# Main.net
KiCad netlist of a schematic drawn in EAGLE
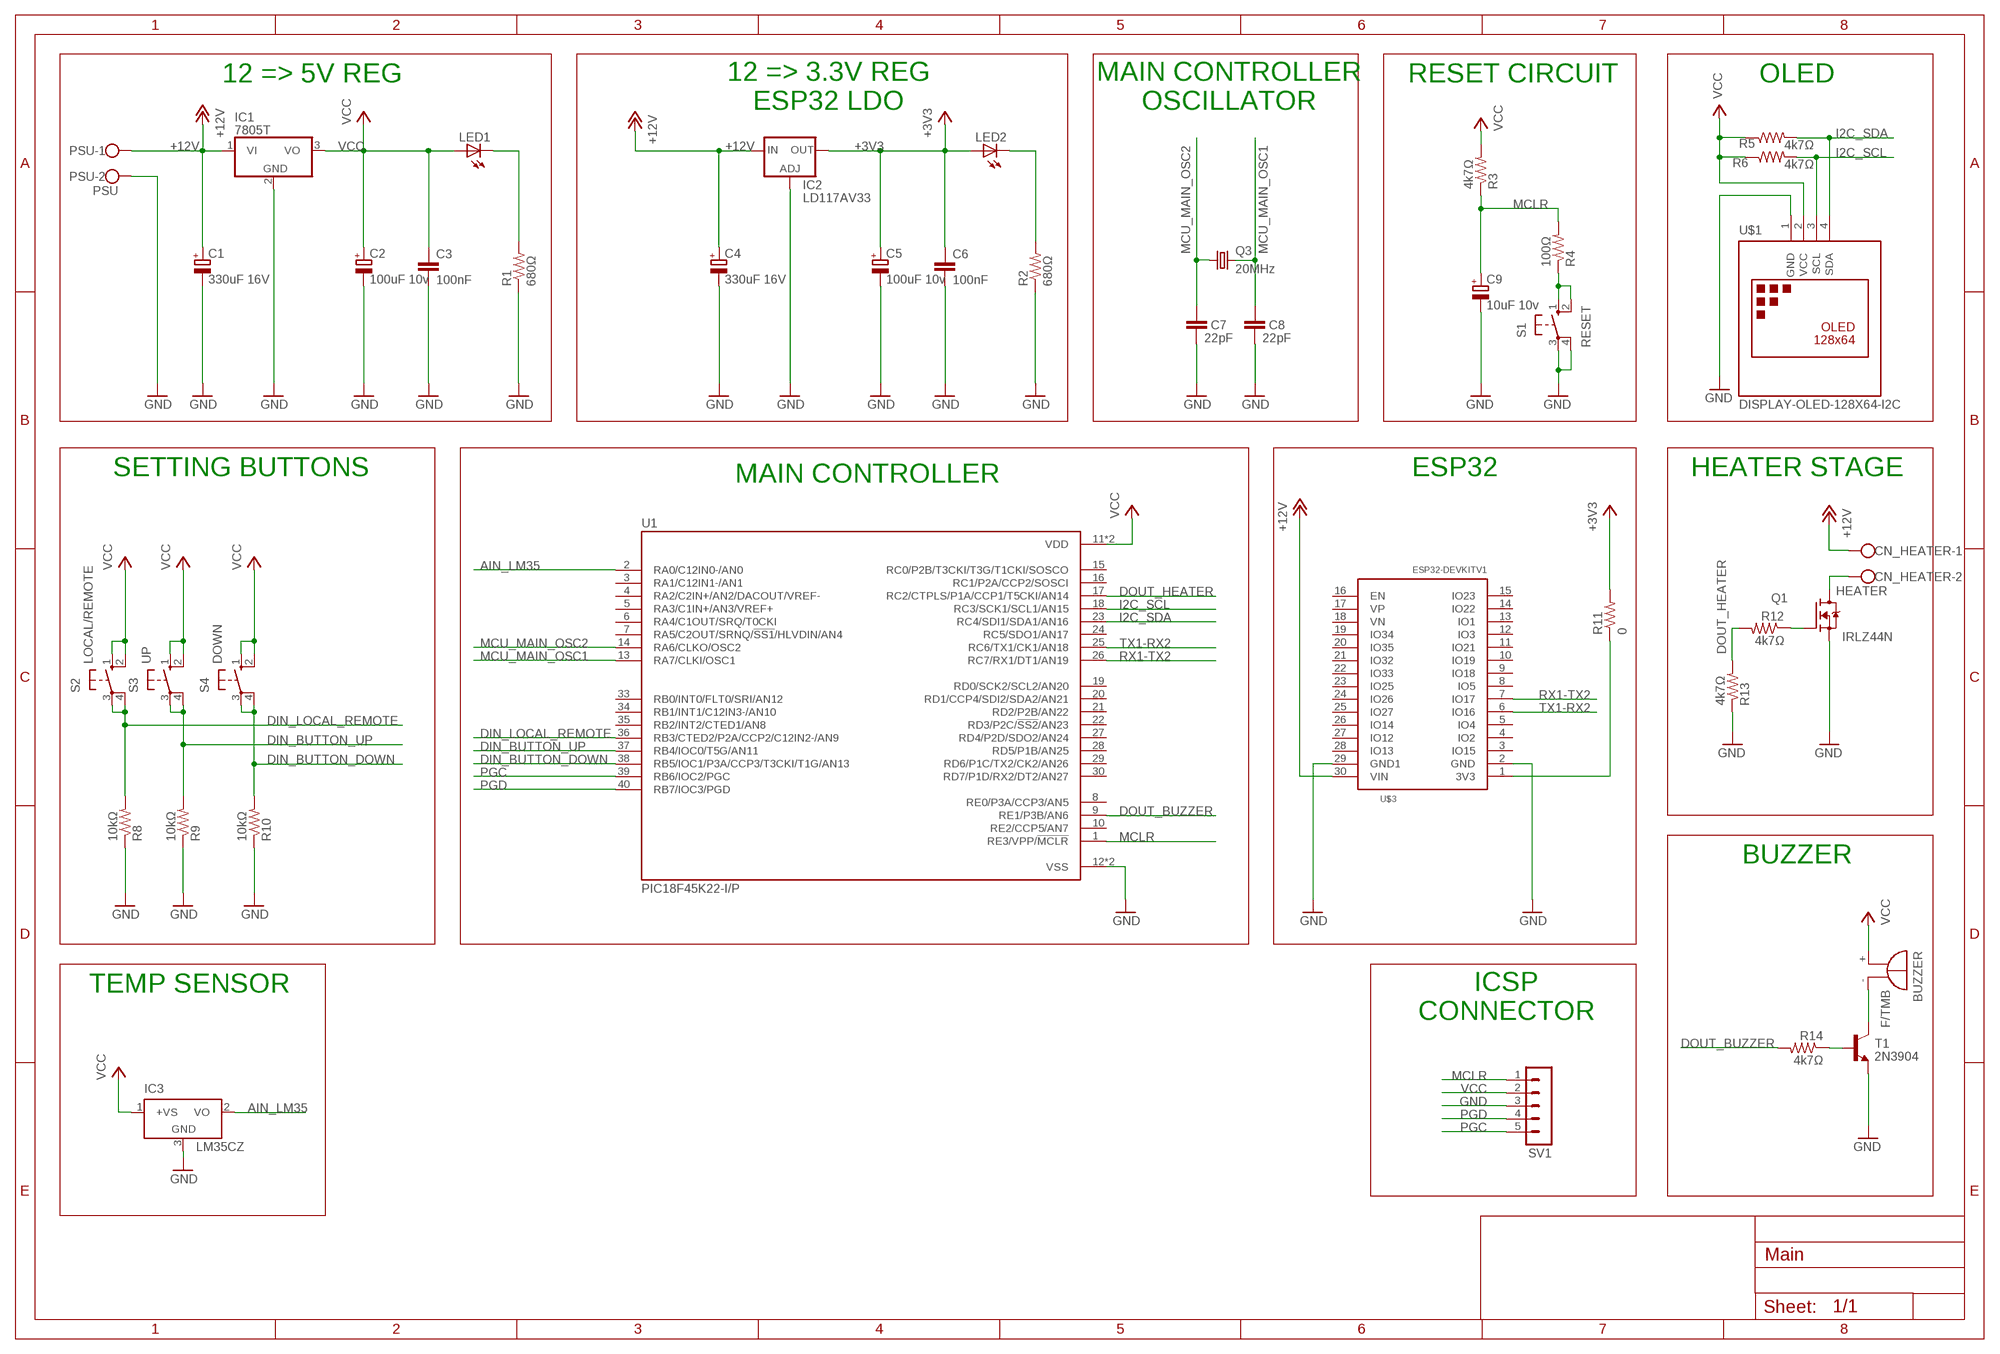
[diagram p0: schematic, sheet 1]

(export (version "E")
  (design (tool "Eeschema 10.0.6"))
  (components
    (comp (ref "BUZZER")
      (value "F/TMB")
      (footprint "eagle-import:F_TMB")
      (libsource (lib "eagle-import") (part "F/TMB"))
    )
    (comp (ref "C1")
      (value "330uF 16V")
      (footprint "eagle-import:E2-5")
      (libsource (lib "eagle-import") (part "CPOL-EUE2-5"))
    )
    (comp (ref "C2")
      (value "100uF 10v")
      (footprint "eagle-import:E2-5")
      (libsource (lib "eagle-import") (part "CPOL-EUE2-5"))
    )
    (comp (ref "C3")
      (value "100nF")
      (footprint "eagle-import:C025-060X050")
      (libsource (lib "eagle-import") (part "C-EU025-060X050"))
    )
    (comp (ref "C4")
      (value "330uF 16V")
      (footprint "eagle-import:E2-5")
      (libsource (lib "eagle-import") (part "CPOL-EUE2-5"))
    )
    (comp (ref "C5")
      (value "100uF 10v")
      (footprint "eagle-import:E2-5")
      (libsource (lib "eagle-import") (part "CPOL-EUE2-5"))
    )
    (comp (ref "C6")
      (value "100nF")
      (footprint "eagle-import:C025-060X050")
      (libsource (lib "eagle-import") (part "C-EU025-060X050"))
    )
    (comp (ref "C7")
      (value "22pF")
      (footprint "eagle-import:C025-024X044")
      (libsource (lib "eagle-import") (part "C-EU025-024X044"))
    )
    (comp (ref "C8")
      (value "22pF")
      (footprint "eagle-import:C025-024X044")
      (libsource (lib "eagle-import") (part "C-EU025-024X044"))
    )
    (comp (ref "C9")
      (value "10uF 10v")
      (footprint "eagle-import:E2-5")
      (libsource (lib "eagle-import") (part "CPOL-EUE2-5"))
    )
    (comp (ref "CN_HEATER")
      (value "HEATER")
      (footprint "eagle-import:W237-102")
      (fields (field (name "MPN") "237-102"))
      (libsource (lib "eagle-import") (part "W237-102"))
    )
    (comp (ref "IC1")
      (value "7805T")
      (footprint "eagle-import:TO220H")
      (libsource (lib "eagle-import") (part "78T05"))
    )
    (comp (ref "IC2")
      (value "LD117AV33")
      (footprint "eagle-import:TO220L1")
      (libsource (lib "eagle-import") (part "LD117A?V33"))
    )
    (comp (ref "IC3")
      (value "LM35CZ")
      (footprint "eagle-import:TO92")
      (libsource (lib "eagle-import") (part "LM35CZ"))
    )
    (comp (ref "LED1")
      (value "LED5MM")
      (footprint "eagle-import:LED5MM")
      (libsource (lib "eagle-import") (part "LED5MM"))
    )
    (comp (ref "LED2")
      (value "LED5MM")
      (footprint "eagle-import:LED5MM")
      (libsource (lib "eagle-import") (part "LED5MM"))
    )
    (comp (ref "PSU")
      (value "PSU")
      (footprint "eagle-import:W237-102")
      (fields (field (name "MPN") "237-102"))
      (libsource (lib "eagle-import") (part "W237-102"))
    )
    (comp (ref "Q1")
      (value "IRLZ44N")
      (footprint "eagle-import:TO254P1054X469X1930-3")
      (fields (field (name "MF") "Infineon / IR"))
      (libsource (lib "eagle-import") (part "IRLZ44N"))
    )
    (comp (ref "Q3")
      (value "20MHz")
      (footprint "eagle-import:HC49_S")
      (libsource (lib "eagle-import") (part "CRYSTALHC49S"))
    )
    (comp (ref "R1")
      (value "680Ω")
      (footprint "eagle-import:0204_7")
      (libsource (lib "eagle-import") (part "R-US_0204/7"))
    )
    (comp (ref "R2")
      (value "680Ω")
      (footprint "eagle-import:0204_7")
      (libsource (lib "eagle-import") (part "R-US_0204/7"))
    )
    (comp (ref "R3")
      (value "4k7Ω")
      (footprint "eagle-import:0204_7")
      (libsource (lib "eagle-import") (part "R-US_0204/7"))
    )
    (comp (ref "R4")
      (value "100Ω")
      (footprint "eagle-import:0204_7")
      (libsource (lib "eagle-import") (part "R-US_0204/7"))
    )
    (comp (ref "R5")
      (value "4k7Ω")
      (footprint "eagle-import:0204_7")
      (libsource (lib "eagle-import") (part "R-US_0204/7"))
    )
    (comp (ref "R6")
      (value "4k7Ω")
      (footprint "eagle-import:0204_7")
      (libsource (lib "eagle-import") (part "R-US_0204/7"))
    )
    (comp (ref "R8")
      (value "10kΩ")
      (footprint "eagle-import:0204_7")
      (libsource (lib "eagle-import") (part "R-US_0204/7"))
    )
    (comp (ref "R9")
      (value "10kΩ")
      (footprint "eagle-import:0204_7")
      (libsource (lib "eagle-import") (part "R-US_0204/7"))
    )
    (comp (ref "R10")
      (value "10kΩ")
      (footprint "eagle-import:0204_7")
      (libsource (lib "eagle-import") (part "R-US_0204/7"))
    )
    (comp (ref "R11")
      (value "0")
      (footprint "eagle-import:0204_7")
      (libsource (lib "eagle-import") (part "R-US_0204/7"))
    )
    (comp (ref "R12")
      (value "4k7Ω")
      (footprint "eagle-import:0204_7")
      (libsource (lib "eagle-import") (part "R-US_0204/7"))
    )
    (comp (ref "R13")
      (value "4k7Ω")
      (footprint "eagle-import:0204_7")
      (libsource (lib "eagle-import") (part "R-US_0204/7"))
    )
    (comp (ref "R14")
      (value "4k7Ω")
      (footprint "eagle-import:0204_7")
      (libsource (lib "eagle-import") (part "R-US_0204/7"))
    )
    (comp (ref "S1")
      (value "RESET")
      (footprint "eagle-import:B3F-10XX")
      (fields (field (name "MPN") "B3F-1000"))
      (libsource (lib "eagle-import") (part "10-XX"))
    )
    (comp (ref "S2")
      (value "LOCAL/REMOTE")
      (footprint "eagle-import:B3F-10XX")
      (fields (field (name "MPN") "B3F-1000"))
      (libsource (lib "eagle-import") (part "10-XX"))
    )
    (comp (ref "S3")
      (value "UP")
      (footprint "eagle-import:B3F-10XX")
      (fields (field (name "MPN") "B3F-1000"))
      (libsource (lib "eagle-import") (part "10-XX"))
    )
    (comp (ref "S4")
      (value "DOWN")
      (footprint "eagle-import:B3F-10XX")
      (fields (field (name "MPN") "B3F-1000"))
      (libsource (lib "eagle-import") (part "10-XX"))
    )
    (comp (ref "SV1")
      (value "MA05-1")
      (footprint "eagle-import:MA05-1")
      (libsource (lib "eagle-import") (part "MA05-1"))
    )
    (comp (ref "T1")
      (value "2N3904")
      (footprint "eagle-import:TO92")
      (libsource (lib "eagle-import") (part "2N3904"))
    )
    (comp (ref "U$1")
      (value "DISPLAY-OLED-128X64-I2C")
      (footprint "eagle-import:DISPLAY-OLED-128X64-I2C")
      (libsource (lib "eagle-import") (part "DISPLAY-OLED-128X64-I2C"))
    )
    (comp (ref "U$3")
      (value "ESP32DEVKITV1")
      (footprint "eagle-import:ESP32-DEVKITV1")
      (libsource (lib "eagle-import") (part "ESP32DEVKITV1"))
    )
    (comp (ref "U1")
      (value "PIC18F45K22-I/P")
      (footprint "eagle-import:DIP1543W47P254L5321H635Q40")
      (fields (field (name "MF") "Microchip"))
      (libsource (lib "eagle-import") (part "PIC18F45K22-I/P"))
    )
  )
  (nets
    (net (code "1") (name "+3V3") (class "Default")
      (node (ref "C5") (pin "+") (pinfunction "+_+") (pintype "passive"))
      (node (ref "C6") (pin "1") (pinfunction "1_1") (pintype "passive"))
      (node (ref "IC2") (pin "2") (pinfunction "OUT_2") (pintype "passive"))
      (node (ref "LED2") (pin "A") (pinfunction "A_A") (pintype "passive"))
      (node (ref "R11") (pin "2") (pinfunction "2_2") (pintype "passive"))
    )
    (net (code "2") (name "+12V") (class "Default")
      (node (ref "C1") (pin "+") (pinfunction "+_+") (pintype "passive"))
      (node (ref "C4") (pin "+") (pinfunction "+_+") (pintype "passive"))
      (node (ref "CN_HEATER") (pin "1") (pinfunction "KL_1") (pintype "passive"))
      (node (ref "IC1") (pin "1") (pinfunction "VI_1") (pintype "input"))
      (node (ref "IC2") (pin "3") (pinfunction "IN_3") (pintype "input"))
      (node (ref "PSU") (pin "1") (pinfunction "KL_1") (pintype "passive"))
      (node (ref "U$3") (pin "30") (pinfunction "VIN_30") (pintype "power_in"))
    )
    (net (code "3") (name "/AIN_LM35") (class "Default")
      (node (ref "IC3") (pin "2") (pinfunction "VO_2") (pintype "input"))
      (node (ref "U1") (pin "2") (pinfunction "RA0/C12IN0-/AN0_2") (pintype "bidirectional"))
    )
    (net (code "4") (name "/DIN_BUTTON_DOWN") (class "Default")
      (node (ref "R10") (pin "2") (pinfunction "2_2") (pintype "passive"))
      (node (ref "S4") (pin "3") (pinfunction "P_3") (pintype "passive"))
      (node (ref "S4") (pin "4") (pinfunction "P1_4") (pintype "passive"))
      (node (ref "U1") (pin "38") (pinfunction "RB5/IOC1/P3A/CCP3/T3CKI/T1G/AN13_38") (pintype "bidirectional"))
    )
    (net (code "5") (name "/DIN_BUTTON_UP") (class "Default")
      (node (ref "R9") (pin "2") (pinfunction "2_2") (pintype "passive"))
      (node (ref "S3") (pin "3") (pinfunction "P_3") (pintype "passive"))
      (node (ref "S3") (pin "4") (pinfunction "P1_4") (pintype "passive"))
      (node (ref "U1") (pin "37") (pinfunction "RB4/IOC0/T5G/AN11_37") (pintype "bidirectional"))
    )
    (net (code "6") (name "/DIN_LOCAL_REMOTE") (class "Default")
      (node (ref "R8") (pin "2") (pinfunction "2_2") (pintype "passive"))
      (node (ref "S2") (pin "3") (pinfunction "P_3") (pintype "passive"))
      (node (ref "S2") (pin "4") (pinfunction "P1_4") (pintype "passive"))
      (node (ref "U1") (pin "36") (pinfunction "RB3/CTED2/P2A/CCP2/C12IN2-/AN9_36") (pintype "bidirectional"))
    )
    (net (code "7") (name "/DOUT_BUZZER") (class "Default")
      (node (ref "R14") (pin "2") (pinfunction "2_2") (pintype "passive"))
      (node (ref "U1") (pin "9") (pinfunction "RE1/P3B/AN6_9") (pintype "bidirectional"))
    )
    (net (code "8") (name "/DOUT_HEATER") (class "Default")
      (node (ref "R12") (pin "2") (pinfunction "2_2") (pintype "passive"))
      (node (ref "R13") (pin "2") (pinfunction "2_2") (pintype "passive"))
      (node (ref "U1") (pin "17") (pinfunction "RC2/CTPLS/P1A/CCP1/T5CKI/AN14_17") (pintype "bidirectional"))
    )
    (net (code "9") (name "/I2C_SCL") (class "Default")
      (node (ref "R6") (pin "2") (pinfunction "2_2") (pintype "passive"))
      (node (ref "U$1") (pin "3") (pinfunction "SCL_3") (pintype "bidirectional"))
      (node (ref "U1") (pin "18") (pinfunction "RC3/SCK1/SCL1/AN15_18") (pintype "bidirectional"))
    )
    (net (code "10") (name "/I2C_SDA") (class "Default")
      (node (ref "R5") (pin "2") (pinfunction "2_2") (pintype "passive"))
      (node (ref "U$1") (pin "4") (pinfunction "SDA_4") (pintype "bidirectional"))
      (node (ref "U1") (pin "23") (pinfunction "RC4/SDI1/SDA1/AN16_23") (pintype "bidirectional"))
    )
    (net (code "11") (name "/MCLR") (class "Default")
      (node (ref "C9") (pin "+") (pinfunction "+_+") (pintype "passive"))
      (node (ref "R3") (pin "1") (pinfunction "1_1") (pintype "passive"))
      (node (ref "R4") (pin "2") (pinfunction "2_2") (pintype "passive"))
      (node (ref "SV1") (pin "1") (pinfunction "1_1") (pintype "passive"))
      (node (ref "U1") (pin "1") (pinfunction "RE3/VPP/~{MCLR}_1") (pintype "bidirectional"))
    )
    (net (code "12") (name "/MCU_MAIN_OSC1") (class "Default")
      (node (ref "C8") (pin "1") (pinfunction "1_1") (pintype "passive"))
      (node (ref "Q3") (pin "2") (pinfunction "2_2") (pintype "passive"))
      (node (ref "U1") (pin "13") (pinfunction "RA7/CLKI/OSC1_13") (pintype "bidirectional"))
    )
    (net (code "13") (name "/MCU_MAIN_OSC2") (class "Default")
      (node (ref "C7") (pin "1") (pinfunction "1_1") (pintype "passive"))
      (node (ref "Q3") (pin "1") (pinfunction "1_1") (pintype "passive"))
      (node (ref "U1") (pin "14") (pinfunction "RA6/CLKO/OSC2_14") (pintype "bidirectional"))
    )
    (net (code "14") (name "/PGC") (class "Default")
      (node (ref "SV1") (pin "5") (pinfunction "5_5") (pintype "passive"))
      (node (ref "U1") (pin "39") (pinfunction "RB6/IOC2/PGC_39") (pintype "bidirectional"))
    )
    (net (code "15") (name "/PGD") (class "Default")
      (node (ref "SV1") (pin "4") (pinfunction "4_4") (pintype "passive"))
      (node (ref "U1") (pin "40") (pinfunction "RB7/IOC3/PGD_40") (pintype "bidirectional"))
    )
    (net (code "16") (name "/RX1-TX2") (class "Default")
      (node (ref "U$3") (pin "7") (pinfunction "IO17_7") (pintype "bidirectional"))
      (node (ref "U1") (pin "26") (pinfunction "RC7/RX1/DT1/AN19_26") (pintype "bidirectional"))
    )
    (net (code "17") (name "/TX1-RX2") (class "Default")
      (node (ref "U$3") (pin "6") (pinfunction "IO16_6") (pintype "bidirectional"))
      (node (ref "U1") (pin "25") (pinfunction "RC6/TX1/CK1/AN18_25") (pintype "bidirectional"))
    )
    (net (code "18") (name "GND") (class "Default")
      (node (ref "C1") (pin "-") (pinfunction "-_-") (pintype "passive"))
      (node (ref "C2") (pin "-") (pinfunction "-_-") (pintype "passive"))
      (node (ref "C3") (pin "2") (pinfunction "2_2") (pintype "passive"))
      (node (ref "C4") (pin "-") (pinfunction "-_-") (pintype "passive"))
      (node (ref "C5") (pin "-") (pinfunction "-_-") (pintype "passive"))
      (node (ref "C6") (pin "2") (pinfunction "2_2") (pintype "passive"))
      (node (ref "C7") (pin "2") (pinfunction "2_2") (pintype "passive"))
      (node (ref "C8") (pin "2") (pinfunction "2_2") (pintype "passive"))
      (node (ref "C9") (pin "-") (pinfunction "-_-") (pintype "passive"))
      (node (ref "IC1") (pin "2") (pinfunction "GND_2") (pintype "passive"))
      (node (ref "IC2") (pin "1") (pinfunction "ADJ_1") (pintype "input"))
      (node (ref "IC3") (pin "3") (pinfunction "GND_3") (pintype "power_in"))
      (node (ref "PSU") (pin "2") (pinfunction "KL_2") (pintype "passive"))
      (node (ref "Q1") (pin "3") (pinfunction "S_3") (pintype "passive"))
      (node (ref "R1") (pin "1") (pinfunction "1_1") (pintype "passive"))
      (node (ref "R10") (pin "1") (pinfunction "1_1") (pintype "passive"))
      (node (ref "R13") (pin "1") (pinfunction "1_1") (pintype "passive"))
      (node (ref "R2") (pin "1") (pinfunction "1_1") (pintype "passive"))
      (node (ref "R8") (pin "1") (pinfunction "1_1") (pintype "passive"))
      (node (ref "R9") (pin "1") (pinfunction "1_1") (pintype "passive"))
      (node (ref "S1") (pin "3") (pinfunction "P_3") (pintype "passive"))
      (node (ref "S1") (pin "4") (pinfunction "P1_4") (pintype "passive"))
      (node (ref "SV1") (pin "3") (pinfunction "3_3") (pintype "passive"))
      (node (ref "T1") (pin "3") (pinfunction "E_3") (pintype "passive"))
      (node (ref "U$1") (pin "1") (pinfunction "GND_1") (pintype "power_in"))
      (node (ref "U$3") (pin "2") (pinfunction "GND_2") (pintype "power_in"))
      (node (ref "U$3") (pin "29") (pinfunction "GND1_29") (pintype "power_in"))
      (node (ref "U1") (pin "12") (pinfunction "VSS_12") (pintype "power_in"))
      (node (ref "U1") (pin "31") (pinfunction "VSS_31") (pintype "power_in"))
    )
    (net (code "19") (name "Net-(CN_HEATERB-KL)") (class "Default")
      (node (ref "CN_HEATER") (pin "2") (pinfunction "KL_2") (pintype "passive"))
      (node (ref "Q1") (pin "2") (pinfunction "D_2") (pintype "passive"))
    )
    (net (code "20") (name "Net-(LED1-C)") (class "Default")
      (node (ref "LED1") (pin "K") (pinfunction "C_K") (pintype "passive"))
      (node (ref "R1") (pin "2") (pinfunction "2_2") (pintype "passive"))
    )
    (net (code "21") (name "Net-(LED2-C)") (class "Default")
      (node (ref "LED2") (pin "K") (pinfunction "C_K") (pintype "passive"))
      (node (ref "R2") (pin "2") (pinfunction "2_2") (pintype "passive"))
    )
    (net (code "22") (name "Net-(Q1-G)") (class "Default")
      (node (ref "Q1") (pin "1") (pinfunction "G_1") (pintype "passive"))
      (node (ref "R12") (pin "1") (pinfunction "1_1") (pintype "passive"))
    )
    (net (code "23") (name "Net-(S1-S)") (class "Default")
      (node (ref "R4") (pin "1") (pinfunction "1_1") (pintype "passive"))
      (node (ref "S1") (pin "1") (pinfunction "S_1") (pintype "passive"))
      (node (ref "S1") (pin "2") (pinfunction "S1_2") (pintype "passive"))
    )
    (net (code "24") (name "Net-(T1-B)") (class "Default")
      (node (ref "R14") (pin "1") (pinfunction "1_1") (pintype "passive"))
      (node (ref "T1") (pin "2") (pinfunction "B_2") (pintype "passive"))
    )
    (net (code "25") (name "Net-(T1-C)") (class "Default")
      (node (ref "BUZZER") (pin "-") (pinfunction "-_-") (pintype "passive"))
      (node (ref "T1") (pin "1") (pinfunction "C_1") (pintype "passive"))
    )
    (net (code "26") (name "Net-(U$3-3V3)") (class "Default")
      (node (ref "R11") (pin "1") (pinfunction "1_1") (pintype "passive"))
      (node (ref "U$3") (pin "1") (pinfunction "3V3_1") (pintype "power_in"))
    )
    (net (code "27") (name "VCC") (class "Default")
      (node (ref "BUZZER") (pin "+") (pinfunction "+_+") (pintype "passive"))
      (node (ref "C2") (pin "+") (pinfunction "+_+") (pintype "passive"))
      (node (ref "C3") (pin "1") (pinfunction "1_1") (pintype "passive"))
      (node (ref "IC1") (pin "3") (pinfunction "VO_3") (pintype "passive"))
      (node (ref "IC3") (pin "1") (pinfunction "+VS_1") (pintype "input"))
      (node (ref "LED1") (pin "A") (pinfunction "A_A") (pintype "passive"))
      (node (ref "R3") (pin "2") (pinfunction "2_2") (pintype "passive"))
      (node (ref "R5") (pin "1") (pinfunction "1_1") (pintype "passive"))
      (node (ref "R6") (pin "1") (pinfunction "1_1") (pintype "passive"))
      (node (ref "S2") (pin "1") (pinfunction "S_1") (pintype "passive"))
      (node (ref "S2") (pin "2") (pinfunction "S1_2") (pintype "passive"))
      (node (ref "S3") (pin "1") (pinfunction "S_1") (pintype "passive"))
      (node (ref "S3") (pin "2") (pinfunction "S1_2") (pintype "passive"))
      (node (ref "S4") (pin "1") (pinfunction "S_1") (pintype "passive"))
      (node (ref "S4") (pin "2") (pinfunction "S1_2") (pintype "passive"))
      (node (ref "SV1") (pin "2") (pinfunction "2_2") (pintype "passive"))
      (node (ref "U$1") (pin "2") (pinfunction "VCC_2") (pintype "power_in"))
      (node (ref "U1") (pin "11") (pinfunction "VDD_11") (pintype "power_in"))
      (node (ref "U1") (pin "32") (pinfunction "VDD_32") (pintype "power_in"))
    )
    (net (code "28") (name "unconnected-(U$3-EN-Pad16)") (class "Default")
      (node (ref "U$3") (pin "16") (pinfunction "EN_16") (pintype "bidirectional"))
    )
    (net (code "29") (name "unconnected-(U$3-IO1-Pad13)") (class "Default")
      (node (ref "U$3") (pin "13") (pinfunction "IO1_13") (pintype "bidirectional"))
    )
    (net (code "30") (name "unconnected-(U$3-IO2-Pad4)") (class "Default")
      (node (ref "U$3") (pin "4") (pinfunction "IO2_4") (pintype "bidirectional"))
    )
    (net (code "31") (name "unconnected-(U$3-IO3-Pad12)") (class "Default")
      (node (ref "U$3") (pin "12") (pinfunction "IO3_12") (pintype "bidirectional"))
    )
    (net (code "32") (name "unconnected-(U$3-IO4-Pad5)") (class "Default")
      (node (ref "U$3") (pin "5") (pinfunction "IO4_5") (pintype "bidirectional"))
    )
    (net (code "33") (name "unconnected-(U$3-IO5-Pad8)") (class "Default")
      (node (ref "U$3") (pin "8") (pinfunction "IO5_8") (pintype "bidirectional"))
    )
    (net (code "34") (name "unconnected-(U$3-IO12-Pad27)") (class "Default")
      (node (ref "U$3") (pin "27") (pinfunction "IO12_27") (pintype "bidirectional"))
    )
    (net (code "35") (name "unconnected-(U$3-IO13-Pad28)") (class "Default")
      (node (ref "U$3") (pin "28") (pinfunction "IO13_28") (pintype "bidirectional"))
    )
    (net (code "36") (name "unconnected-(U$3-IO14-Pad26)") (class "Default")
      (node (ref "U$3") (pin "26") (pinfunction "IO14_26") (pintype "bidirectional"))
    )
    (net (code "37") (name "unconnected-(U$3-IO15-Pad3)") (class "Default")
      (node (ref "U$3") (pin "3") (pinfunction "IO15_3") (pintype "bidirectional"))
    )
    (net (code "38") (name "unconnected-(U$3-IO18-Pad9)") (class "Default")
      (node (ref "U$3") (pin "9") (pinfunction "IO18_9") (pintype "bidirectional"))
    )
    (net (code "39") (name "unconnected-(U$3-IO19-Pad10)") (class "Default")
      (node (ref "U$3") (pin "10") (pinfunction "IO19_10") (pintype "bidirectional"))
    )
    (net (code "40") (name "unconnected-(U$3-IO21-Pad11)") (class "Default")
      (node (ref "U$3") (pin "11") (pinfunction "IO21_11") (pintype "bidirectional"))
    )
    (net (code "41") (name "unconnected-(U$3-IO22-Pad14)") (class "Default")
      (node (ref "U$3") (pin "14") (pinfunction "IO22_14") (pintype "bidirectional"))
    )
    (net (code "42") (name "unconnected-(U$3-IO23-Pad15)") (class "Default")
      (node (ref "U$3") (pin "15") (pinfunction "IO23_15") (pintype "bidirectional"))
    )
    (net (code "43") (name "unconnected-(U$3-IO25-Pad23)") (class "Default")
      (node (ref "U$3") (pin "23") (pinfunction "IO25_23") (pintype "bidirectional"))
    )
    (net (code "44") (name "unconnected-(U$3-IO26-Pad24)") (class "Default")
      (node (ref "U$3") (pin "24") (pinfunction "IO26_24") (pintype "bidirectional"))
    )
    (net (code "45") (name "unconnected-(U$3-IO27-Pad25)") (class "Default")
      (node (ref "U$3") (pin "25") (pinfunction "IO27_25") (pintype "bidirectional"))
    )
    (net (code "46") (name "unconnected-(U$3-IO32-Pad21)") (class "Default")
      (node (ref "U$3") (pin "21") (pinfunction "IO32_21") (pintype "bidirectional"))
    )
    (net (code "47") (name "unconnected-(U$3-IO33-Pad22)") (class "Default")
      (node (ref "U$3") (pin "22") (pinfunction "IO33_22") (pintype "bidirectional"))
    )
    (net (code "48") (name "unconnected-(U$3-IO34-Pad19)") (class "Default")
      (node (ref "U$3") (pin "19") (pinfunction "IO34_19") (pintype "bidirectional"))
    )
    (net (code "49") (name "unconnected-(U$3-IO35-Pad20)") (class "Default")
      (node (ref "U$3") (pin "20") (pinfunction "IO35_20") (pintype "bidirectional"))
    )
    (net (code "50") (name "unconnected-(U$3-VN-Pad18)") (class "Default")
      (node (ref "U$3") (pin "18") (pinfunction "VN_18") (pintype "bidirectional"))
    )
    (net (code "51") (name "unconnected-(U$3-VP-Pad17)") (class "Default")
      (node (ref "U$3") (pin "17") (pinfunction "VP_17") (pintype "bidirectional"))
    )
    (net (code "52") (name "unconnected-(U1-RA1{slash}C12IN1-{slash}AN1-Pad3)") (class "Default")
      (node (ref "U1") (pin "3") (pinfunction "RA1/C12IN1-/AN1_3") (pintype "bidirectional"))
    )
    (net (code "53") (name "unconnected-(U1-RA2{slash}C2IN+{slash}AN2{slash}DACOUT{slash}VREF--Pad4)") (class "Default")
      (node (ref "U1") (pin "4") (pinfunction "RA2/C2IN+/AN2/DACOUT/VREF-_4") (pintype "bidirectional"))
    )
    (net (code "54") (name "unconnected-(U1-RA3{slash}C1IN+{slash}AN3{slash}VREF+-Pad5)") (class "Default")
      (node (ref "U1") (pin "5") (pinfunction "RA3/C1IN+/AN3/VREF+_5") (pintype "bidirectional"))
    )
    (net (code "55") (name "unconnected-(U1-RA4{slash}C1OUT{slash}SRQ{slash}T0CKI-Pad6)") (class "Default")
      (node (ref "U1") (pin "6") (pinfunction "RA4/C1OUT/SRQ/T0CKI_6") (pintype "bidirectional"))
    )
    (net (code "56") (name "unconnected-(U1-RA5{slash}C2OUT{slash}SRNQ{slash}~{SS1}{slash}HLVDIN{slash}AN4-Pad7)") (class "Default")
      (node (ref "U1") (pin "7") (pinfunction "RA5/C2OUT/SRNQ/~{SS1}/HLVDIN/AN4_7") (pintype "bidirectional"))
    )
    (net (code "57") (name "unconnected-(U1-RB0{slash}INT0{slash}FLT0{slash}SRI{slash}AN12-Pad33)") (class "Default")
      (node (ref "U1") (pin "33") (pinfunction "RB0/INT0/FLT0/SRI/AN12_33") (pintype "bidirectional"))
    )
    (net (code "58") (name "unconnected-(U1-RB1{slash}INT1{slash}C12IN3-{slash}AN10-Pad34)") (class "Default")
      (node (ref "U1") (pin "34") (pinfunction "RB1/INT1/C12IN3-/AN10_34") (pintype "bidirectional"))
    )
    (net (code "59") (name "unconnected-(U1-RB2{slash}INT2{slash}CTED1{slash}AN8-Pad35)") (class "Default")
      (node (ref "U1") (pin "35") (pinfunction "RB2/INT2/CTED1/AN8_35") (pintype "bidirectional"))
    )
    (net (code "60") (name "unconnected-(U1-RC0{slash}P2B{slash}T3CKI{slash}T3G{slash}T1CKI{slash}SOSCO-Pad15)") (class "Default")
      (node (ref "U1") (pin "15") (pinfunction "RC0/P2B/T3CKI/T3G/T1CKI/SOSCO_15") (pintype "bidirectional"))
    )
    (net (code "61") (name "unconnected-(U1-RC1{slash}P2A{slash}CCP2{slash}SOSCI-Pad16)") (class "Default")
      (node (ref "U1") (pin "16") (pinfunction "RC1/P2A/CCP2/SOSCI_16") (pintype "bidirectional"))
    )
    (net (code "62") (name "unconnected-(U1-RC5{slash}SDO1{slash}AN17-Pad24)") (class "Default")
      (node (ref "U1") (pin "24") (pinfunction "RC5/SDO1/AN17_24") (pintype "bidirectional"))
    )
    (net (code "63") (name "unconnected-(U1-RD0{slash}SCK2{slash}SCL2{slash}AN20-Pad19)") (class "Default")
      (node (ref "U1") (pin "19") (pinfunction "RD0/SCK2/SCL2/AN20_19") (pintype "bidirectional"))
    )
    (net (code "64") (name "unconnected-(U1-RD1{slash}CCP4{slash}SDI2{slash}SDA2{slash}AN21-Pad20)") (class "Default")
      (node (ref "U1") (pin "20") (pinfunction "RD1/CCP4/SDI2/SDA2/AN21_20") (pintype "bidirectional"))
    )
    (net (code "65") (name "unconnected-(U1-RD2{slash}P2B{slash}AN22-Pad21)") (class "Default")
      (node (ref "U1") (pin "21") (pinfunction "RD2/P2B/AN22_21") (pintype "bidirectional"))
    )
    (net (code "66") (name "unconnected-(U1-RD3{slash}P2C{slash}~{SS2}{slash}AN23-Pad22)") (class "Default")
      (node (ref "U1") (pin "22") (pinfunction "RD3/P2C/~{SS2}/AN23_22") (pintype "bidirectional"))
    )
    (net (code "67") (name "unconnected-(U1-RD4{slash}P2D{slash}SDO2{slash}AN24-Pad27)") (class "Default")
      (node (ref "U1") (pin "27") (pinfunction "RD4/P2D/SDO2/AN24_27") (pintype "bidirectional"))
    )
    (net (code "68") (name "unconnected-(U1-RD5{slash}P1B{slash}AN25-Pad28)") (class "Default")
      (node (ref "U1") (pin "28") (pinfunction "RD5/P1B/AN25_28") (pintype "bidirectional"))
    )
    (net (code "69") (name "unconnected-(U1-RD6{slash}P1C{slash}TX2{slash}CK2{slash}AN26-Pad29)") (class "Default")
      (node (ref "U1") (pin "29") (pinfunction "RD6/P1C/TX2/CK2/AN26_29") (pintype "bidirectional"))
    )
    (net (code "70") (name "unconnected-(U1-RD7{slash}P1D{slash}RX2{slash}DT2{slash}AN27-Pad30)") (class "Default")
      (node (ref "U1") (pin "30") (pinfunction "RD7/P1D/RX2/DT2/AN27_30") (pintype "bidirectional"))
    )
    (net (code "71") (name "unconnected-(U1-RE0{slash}P3A{slash}CCP3{slash}AN5-Pad8)") (class "Default")
      (node (ref "U1") (pin "8") (pinfunction "RE0/P3A/CCP3/AN5_8") (pintype "bidirectional"))
    )
    (net (code "72") (name "unconnected-(U1-RE2{slash}CCP5{slash}AN7-Pad10)") (class "Default")
      (node (ref "U1") (pin "10") (pinfunction "RE2/CCP5/AN7_10") (pintype "bidirectional"))
    )
  )
)
